# Circuito_lm386.net
KiCad netlist of a schematic drawn in EAGLE
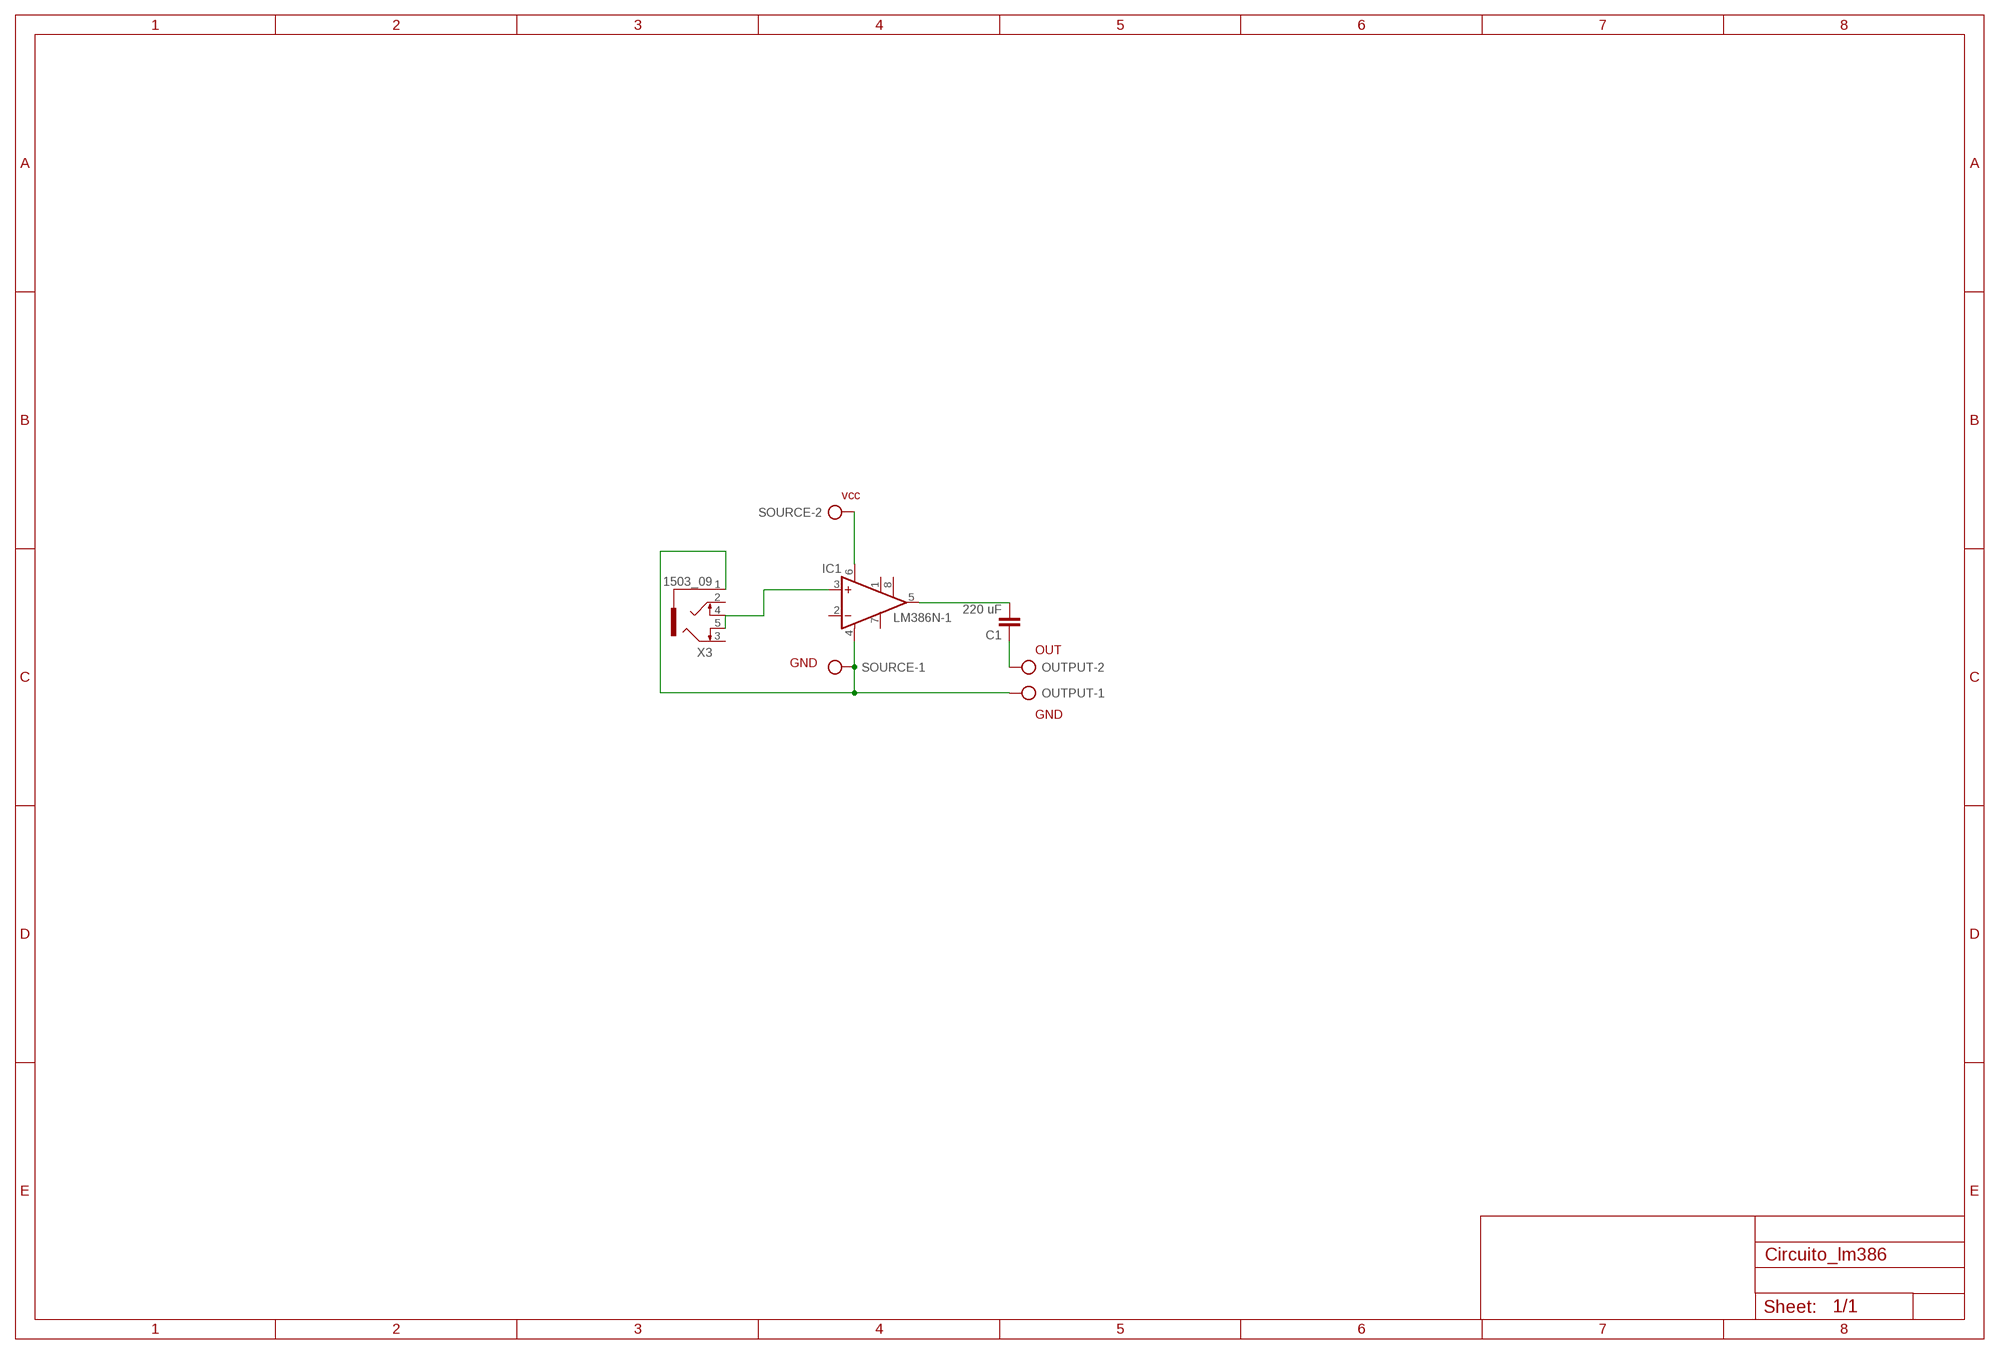
[diagram p0: schematic, sheet 1]

(export (version "E")
  (design (tool "Eeschema 10.0.6"))
  (components
    (comp (ref "C1")
      (value "220 uF")
      (footprint "eagle-import:C5B3")
      (libsource (lib "eagle-import") (part "C5/3"))
    )
    (comp (ref "IC1")
      (value "LM386N-1")
      (footprint "eagle-import:DIL08")
      (libsource (lib "eagle-import") (part "LM386?-N1"))
    )
    (comp (ref "OUTPUT")
      (value "AK500/2-H")
      (footprint "eagle-import:AK500_2-H")
      (libsource (lib "eagle-import") (part "AK500/2-H"))
    )
    (comp (ref "SOURCE")
      (value "AK500/2-H")
      (footprint "eagle-import:AK500_2-H")
      (libsource (lib "eagle-import") (part "AK500/2-H"))
    )
    (comp (ref "X3")
      (value "1503_09")
      (footprint "eagle-import:1503_09")
      (libsource (lib "eagle-import") (part "1503_09"))
    )
  )
  (nets
    (net (code "1") (name "Net-(IC1-+IN)") (class "Default")
      (node (ref "IC1") (pin "3") (pinfunction "+IN_3") (pintype "input"))
      (node (ref "X3") (pin "4") (pinfunction "4_4") (pintype "passive"))
      (node (ref "X3") (pin "5") (pinfunction "5_5") (pintype "passive"))
    )
    (net (code "2") (name "Net-(IC1-GND)") (class "Default")
      (node (ref "IC1") (pin "4") (pinfunction "GND_4") (pintype "power_in"))
      (node (ref "OUTPUT") (pin "1") (pinfunction "KL_1") (pintype "passive"))
      (node (ref "SOURCE") (pin "1") (pinfunction "KL_1") (pintype "passive"))
      (node (ref "X3") (pin "1") (pinfunction "1_1") (pintype "passive"))
    )
    (net (code "3") (name "Net-(IC1-OUT)") (class "Default")
      (node (ref "C1") (pin "2") (pinfunction "2_2") (pintype "passive"))
      (node (ref "IC1") (pin "5") (pinfunction "OUT_5") (pintype "output"))
    )
    (net (code "4") (name "Net-(IC1-VS)") (class "Default")
      (node (ref "IC1") (pin "6") (pinfunction "VS_6") (pintype "power_in"))
      (node (ref "SOURCE") (pin "2") (pinfunction "KL_2") (pintype "passive"))
    )
    (net (code "5") (name "Net-(OUTPUTB-KL)") (class "Default")
      (node (ref "C1") (pin "1") (pinfunction "1_1") (pintype "passive"))
      (node (ref "OUTPUT") (pin "2") (pinfunction "KL_2") (pintype "passive"))
    )
    (net (code "6") (name "unconnected-(IC1--IN-Pad2)") (class "Default")
      (node (ref "IC1") (pin "2") (pinfunction "-IN_2") (pintype "input"))
    )
    (net (code "7") (name "unconnected-(IC1-BYPASS-Pad7)") (class "Default")
      (node (ref "IC1") (pin "7") (pinfunction "BYPASS_7") (pintype "passive"))
    )
    (net (code "8") (name "unconnected-(IC1-GAIN-Pad1)") (class "Default")
      (node (ref "IC1") (pin "1") (pinfunction "GAIN_1") (pintype "passive"))
    )
    (net (code "9") (name "unconnected-(IC1-GAIN-Pad8)") (class "Default")
      (node (ref "IC1") (pin "8") (pinfunction "GAIN_8") (pintype "passive"))
    )
    (net (code "10") (name "unconnected-(X3-Pad2)") (class "Default")
      (node (ref "X3") (pin "2") (pinfunction "2_2") (pintype "passive"))
    )
    (net (code "11") (name "unconnected-(X3-Pad3)") (class "Default")
      (node (ref "X3") (pin "3") (pinfunction "3_3") (pintype "passive"))
    )
  )
)
